# dac.net
KiCad netlist of a schematic drawn in EAGLE
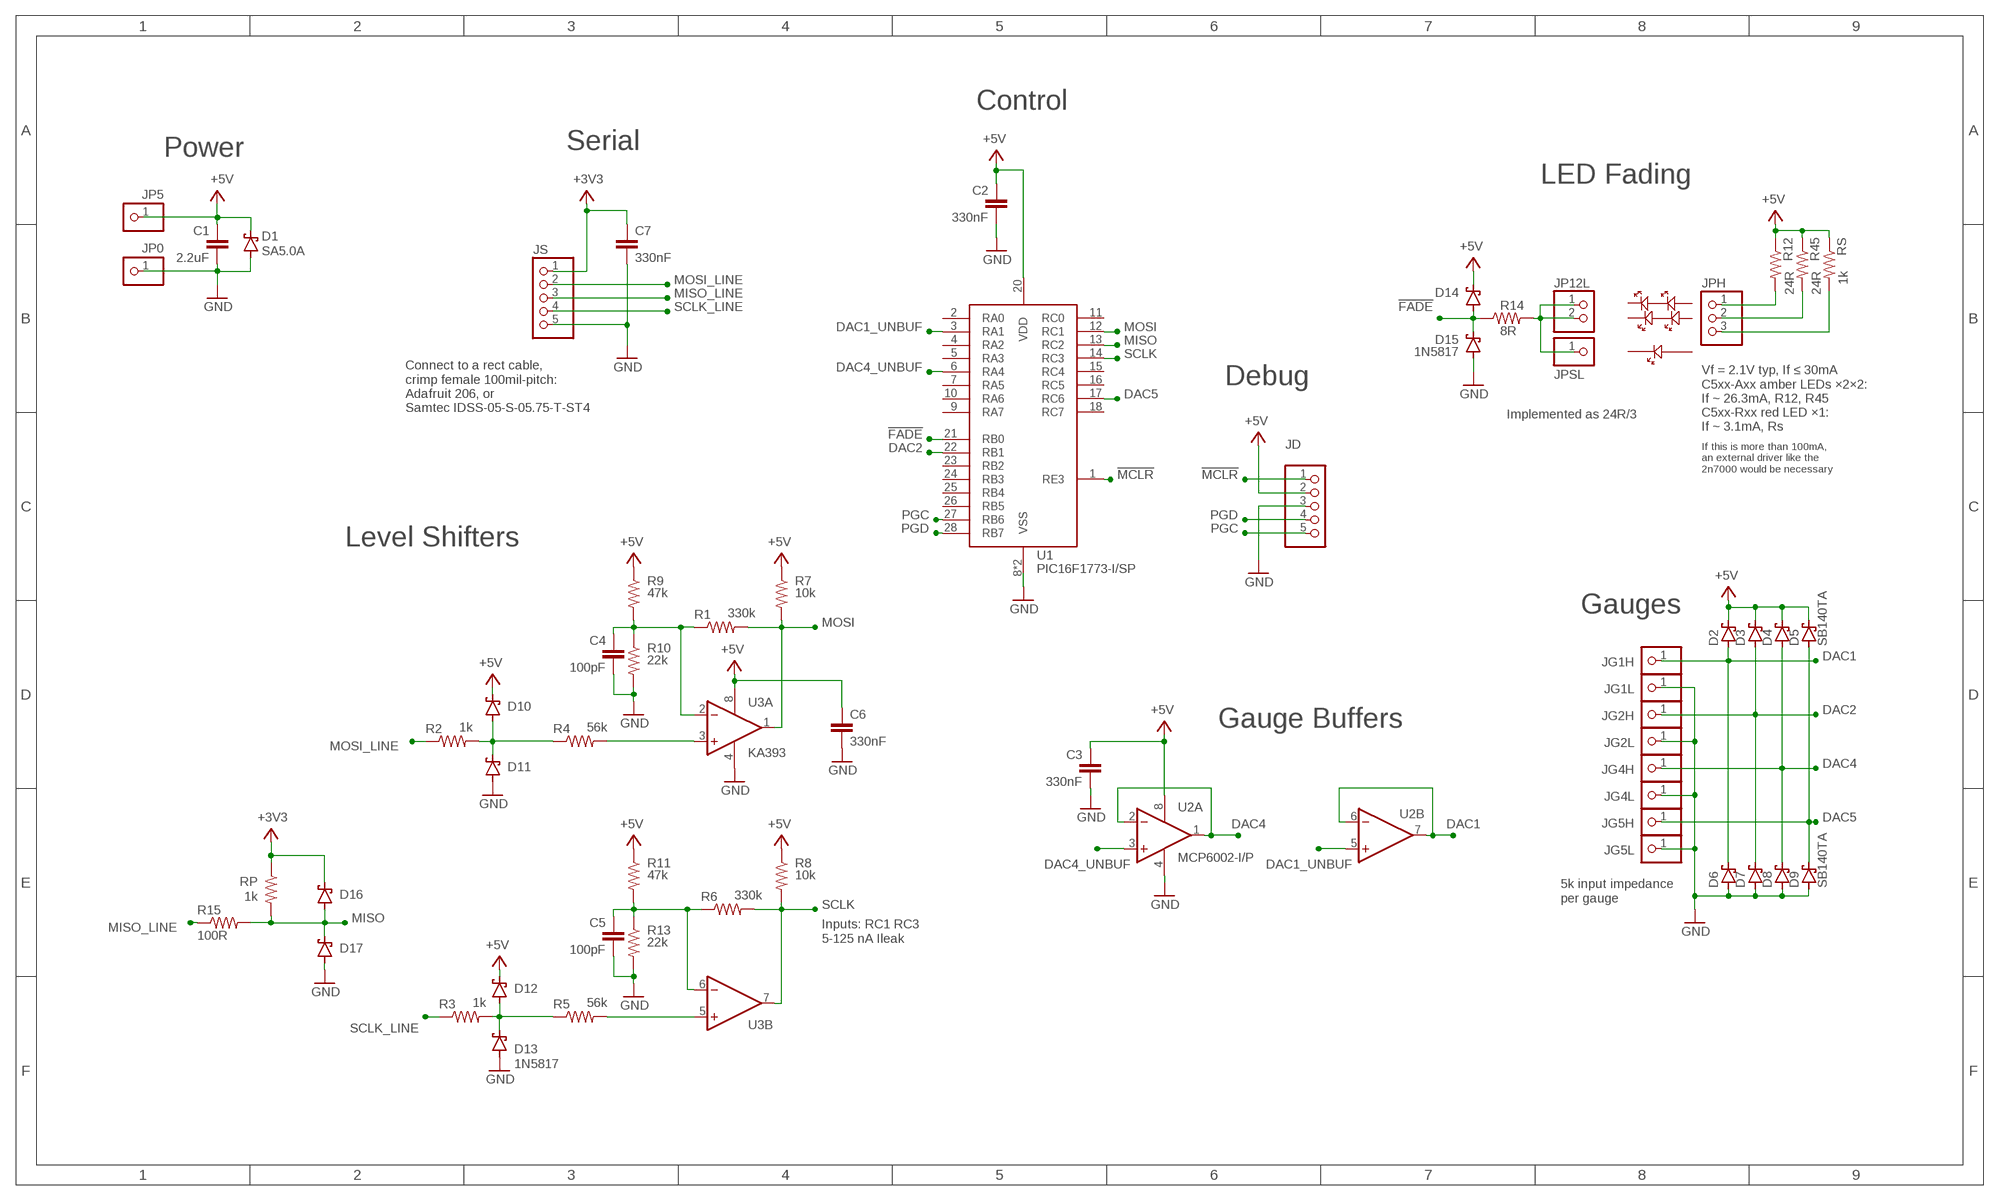
[diagram p0: schematic, sheet 1]

(export (version "E")
  (design (tool "Eeschema 10.0.6"))
  (components
    (comp (ref "C1")
      (value "2.2uF")
      (footprint "eagle-import:C050-024X044")
      (libsource (lib "eagle-import") (part "C-EU050-024X044"))
    )
    (comp (ref "C2")
      (value "330nF")
      (footprint "eagle-import:C050-024X044")
      (libsource (lib "eagle-import") (part "C-EU050-024X044"))
    )
    (comp (ref "C3")
      (value "330nF")
      (footprint "eagle-import:C050-024X044")
      (libsource (lib "eagle-import") (part "C-EU050-024X044"))
    )
    (comp (ref "C4")
      (value "100pF")
      (footprint "eagle-import:C050-024X044")
      (libsource (lib "eagle-import") (part "C-EU050-024X044"))
    )
    (comp (ref "C5")
      (value "100pF")
      (footprint "eagle-import:C050-024X044")
      (libsource (lib "eagle-import") (part "C-EU050-024X044"))
    )
    (comp (ref "C6")
      (value "330nF")
      (footprint "eagle-import:C050-024X044")
      (libsource (lib "eagle-import") (part "C-EU050-024X044"))
    )
    (comp (ref "C7")
      (value "330nF")
      (footprint "eagle-import:C050-024X044")
      (libsource (lib "eagle-import") (part "C-EU050-024X044"))
    )
    (comp (ref "D1")
      (value "SA5.0A")
      (footprint "eagle-import:ZDIO-2.5")
      (libsource (lib "eagle-import") (part "SB-V120"))
    )
    (comp (ref "D2")
      (value "SB140TA")
      (footprint "eagle-import:DO41-7.6")
      (libsource (lib "eagle-import") (part "SB140"))
    )
    (comp (ref "D3")
      (value "SB140TA")
      (footprint "eagle-import:DO41-7.6")
      (libsource (lib "eagle-import") (part "SB140"))
    )
    (comp (ref "D4")
      (value "SB140TA")
      (footprint "eagle-import:DO41-7.6")
      (libsource (lib "eagle-import") (part "SB140"))
    )
    (comp (ref "D5")
      (value "SB140TA")
      (footprint "eagle-import:DO41-7.6")
      (libsource (lib "eagle-import") (part "SB140"))
    )
    (comp (ref "D6")
      (value "SB140TA")
      (footprint "eagle-import:DO41-7.6")
      (libsource (lib "eagle-import") (part "SB140"))
    )
    (comp (ref "D7")
      (value "SB140TA")
      (footprint "eagle-import:DO41-7.6")
      (libsource (lib "eagle-import") (part "1N5817-B"))
    )
    (comp (ref "D8")
      (value "SB140TA")
      (footprint "eagle-import:DO41-7.6")
      (libsource (lib "eagle-import") (part "1N5817-B"))
    )
    (comp (ref "D9")
      (value "SB140TA")
      (footprint "eagle-import:DO41-7.6")
      (libsource (lib "eagle-import") (part "1N5817-B"))
    )
    (comp (ref "D10")
      (value "1N5817-H76")
      (footprint "eagle-import:DO41-7.6")
      (libsource (lib "eagle-import") (part "1N581-H767"))
    )
    (comp (ref "D11")
      (value "1N5817-V")
      (footprint "eagle-import:ZDIO-2.5")
      (libsource (lib "eagle-import") (part "1N581-V7"))
    )
    (comp (ref "D12")
      (value "1N5817-T")
      (footprint "eagle-import:DO41-7.6")
      (libsource (lib "eagle-import") (part "1N5817-T"))
    )
    (comp (ref "D13")
      (value "1N5817")
      (footprint "eagle-import:DO41-10")
      (libsource (lib "eagle-import") (part "1N581-H107"))
    )
    (comp (ref "D14")
      (value "1N5817")
      (footprint "eagle-import:ZDIO-2.5")
      (libsource (lib "eagle-import") (part "SB-V140"))
    )
    (comp (ref "D15")
      (value "1N5817")
      (footprint "eagle-import:ZDIO-2.5")
      (libsource (lib "eagle-import") (part "SB-V140"))
    )
    (comp (ref "D16")
      (value "1N5817-T")
      (footprint "eagle-import:DO41-7.6")
      (libsource (lib "eagle-import") (part "1N5817-T"))
    )
    (comp (ref "D17")
      (value "1N5817-T")
      (footprint "eagle-import:DO41-7.6")
      (libsource (lib "eagle-import") (part "1N5817-T"))
    )
    (comp (ref "JD")
      (value "PINHD-1X5")
      (footprint "eagle-import:1X05")
      (libsource (lib "eagle-import") (part "PINHD-1X5"))
    )
    (comp (ref "JG1H")
      (value "PINHD-1X1")
      (footprint "eagle-import:1X01")
      (libsource (lib "eagle-import") (part "PINHD-1X1"))
    )
    (comp (ref "JG1L")
      (value "PINHD-1X1")
      (footprint "eagle-import:1X01")
      (libsource (lib "eagle-import") (part "PINHD-1X1"))
    )
    (comp (ref "JG2H")
      (value "PINHD-1X1")
      (footprint "eagle-import:1X01")
      (libsource (lib "eagle-import") (part "PINHD-1X1"))
    )
    (comp (ref "JG2L")
      (value "PINHD-1X1")
      (footprint "eagle-import:1X01")
      (libsource (lib "eagle-import") (part "PINHD-1X1"))
    )
    (comp (ref "JG4H")
      (value "PINHD-1X1")
      (footprint "eagle-import:1X01")
      (libsource (lib "eagle-import") (part "PINHD-1X1"))
    )
    (comp (ref "JG4L")
      (value "PINHD-1X1")
      (footprint "eagle-import:1X01")
      (libsource (lib "eagle-import") (part "PINHD-1X1"))
    )
    (comp (ref "JG5H")
      (value "PINHD-1X1")
      (footprint "eagle-import:1X01")
      (libsource (lib "eagle-import") (part "PINHD-1X1"))
    )
    (comp (ref "JG5L")
      (value "PINHD-1X1")
      (footprint "eagle-import:1X01")
      (libsource (lib "eagle-import") (part "PINHD-1X1"))
    )
    (comp (ref "JP0")
      (value "PINHD-1X1")
      (footprint "eagle-import:1X01")
      (libsource (lib "eagle-import") (part "PINHD-1X1"))
    )
    (comp (ref "JP5")
      (value "PINHD-1X1")
      (footprint "eagle-import:1X01")
      (libsource (lib "eagle-import") (part "PINHD-1X1"))
    )
    (comp (ref "JP12L")
      (value "PINHD-1X2")
      (footprint "eagle-import:1X02")
      (libsource (lib "eagle-import") (part "PINHD-1X2"))
    )
    (comp (ref "JPH")
      (value "PINHD-1X3")
      (footprint "eagle-import:1X03")
      (libsource (lib "eagle-import") (part "PINHD-1X3"))
    )
    (comp (ref "JPSL")
      (value "PINHD-1X1")
      (footprint "eagle-import:1X01")
      (libsource (lib "eagle-import") (part "PINHD-1X1"))
    )
    (comp (ref "JS")
      (value "PINHD-1X5")
      (footprint "eagle-import:1X05")
      (libsource (lib "eagle-import") (part "PINHD-1X5"))
    )
    (comp (ref "R1")
      (value "330k")
      (footprint "eagle-import:0207_2V")
      (libsource (lib "eagle-import") (part "R-US_0207/2V"))
    )
    (comp (ref "R2")
      (value "1k")
      (footprint "eagle-import:0204_7")
      (libsource (lib "eagle-import") (part "R-US_0204/7"))
    )
    (comp (ref "R3")
      (value "1k")
      (footprint "eagle-import:0207_10")
      (libsource (lib "eagle-import") (part "R-US_0207/10"))
    )
    (comp (ref "R4")
      (value "56k")
      (footprint "eagle-import:0207_10")
      (libsource (lib "eagle-import") (part "R-US_0207/10"))
    )
    (comp (ref "R5")
      (value "56k")
      (footprint "eagle-import:0207_12")
      (libsource (lib "eagle-import") (part "R-US_0207/12"))
    )
    (comp (ref "R6")
      (value "330k")
      (footprint "eagle-import:0207_2V")
      (libsource (lib "eagle-import") (part "R-US_0207/2V"))
    )
    (comp (ref "R7")
      (value "10k")
      (footprint "eagle-import:0207_2V")
      (libsource (lib "eagle-import") (part "R-US_0207/2V"))
    )
    (comp (ref "R8")
      (value "10k")
      (footprint "eagle-import:0207_2V")
      (libsource (lib "eagle-import") (part "R-US_0207/2V"))
    )
    (comp (ref "R9")
      (value "47k")
      (footprint "eagle-import:0207_7")
      (libsource (lib "eagle-import") (part "R-US_0207/7"))
    )
    (comp (ref "R10")
      (value "22k")
      (footprint "eagle-import:0207_5V")
      (libsource (lib "eagle-import") (part "R-US_0207/5V"))
    )
    (comp (ref "R11")
      (value "47k")
      (footprint "eagle-import:0207_5V")
      (libsource (lib "eagle-import") (part "R-US_0207/5V"))
    )
    (comp (ref "R12")
      (value "24R")
      (footprint "eagle-import:0207_2V")
      (libsource (lib "eagle-import") (part "R-US_0207/2V"))
    )
    (comp (ref "R13")
      (value "22k")
      (footprint "eagle-import:0207_5V")
      (libsource (lib "eagle-import") (part "R-US_0207/5V"))
    )
    (comp (ref "R14")
      (value "8R")
      (footprint "eagle-import:0207_15")
      (libsource (lib "eagle-import") (part "R-US_0207/15"))
    )
    (comp (ref "R15")
      (value "100R")
      (footprint "eagle-import:0207_10")
      (libsource (lib "eagle-import") (part "R-US_0207/10"))
    )
    (comp (ref "R45")
      (value "24R")
      (footprint "eagle-import:0207_2V")
      (libsource (lib "eagle-import") (part "R-US_0207/2V"))
    )
    (comp (ref "RP")
      (value "1k")
      (footprint "eagle-import:0207_5V")
      (libsource (lib "eagle-import") (part "R-US_0207/5V"))
    )
    (comp (ref "RS")
      (value "1k")
      (footprint "eagle-import:0207_2V")
      (libsource (lib "eagle-import") (part "R-US_0207/2V"))
    )
    (comp (ref "U1")
      (value "PIC16F1773-I/SP")
      (footprint "eagle-import:DIL28-3")
      (libsource (lib "eagle-import") (part "PIC16F177/SP3-I"))
    )
    (comp (ref "U2")
      (value "MCP6002-I/P")
      (footprint "eagle-import:DIL08")
      (libsource (lib "eagle-import") (part "MCP602P"))
    )
    (comp (ref "U3")
      (value "KA393")
      (footprint "eagle-import:DIL08")
      (libsource (lib "eagle-import") (part "LM393N"))
    )
  )
  (nets
    (net (code "1") (name "+3V3") (class "Default")
      (node (ref "C7") (pin "1") (pinfunction "1_1") (pintype "passive"))
      (node (ref "D16") (pin "C") (pinfunction "C_C") (pintype "passive"))
      (node (ref "JS") (pin "1") (pinfunction "1_1") (pintype "passive"))
      (node (ref "RP") (pin "1") (pinfunction "1_1") (pintype "passive"))
    )
    (net (code "2") (name "+5V") (class "Default")
      (node (ref "C1") (pin "1") (pinfunction "1_1") (pintype "passive"))
      (node (ref "C2") (pin "1") (pinfunction "1_1") (pintype "passive"))
      (node (ref "C3") (pin "1") (pinfunction "1_1") (pintype "passive"))
      (node (ref "C6") (pin "1") (pinfunction "1_1") (pintype "passive"))
      (node (ref "D1") (pin "C") (pinfunction "C_C") (pintype "passive"))
      (node (ref "D10") (pin "C") (pinfunction "C_C") (pintype "passive"))
      (node (ref "D12") (pin "C") (pinfunction "C_C") (pintype "passive"))
      (node (ref "D14") (pin "C") (pinfunction "C_C") (pintype "passive"))
      (node (ref "D2") (pin "C") (pinfunction "C_C") (pintype "passive"))
      (node (ref "D3") (pin "C") (pinfunction "C_C") (pintype "passive"))
      (node (ref "D4") (pin "C") (pinfunction "C_C") (pintype "passive"))
      (node (ref "D5") (pin "C") (pinfunction "C_C") (pintype "passive"))
      (node (ref "JD") (pin "2") (pinfunction "2_2") (pintype "passive"))
      (node (ref "JP5") (pin "1") (pinfunction "1_1") (pintype "passive"))
      (node (ref "R11") (pin "1") (pinfunction "1_1") (pintype "passive"))
      (node (ref "R12") (pin "1") (pinfunction "1_1") (pintype "passive"))
      (node (ref "R45") (pin "1") (pinfunction "1_1") (pintype "passive"))
      (node (ref "R7") (pin "1") (pinfunction "1_1") (pintype "passive"))
      (node (ref "R8") (pin "1") (pinfunction "1_1") (pintype "passive"))
      (node (ref "R9") (pin "1") (pinfunction "1_1") (pintype "passive"))
      (node (ref "RS") (pin "1") (pinfunction "1_1") (pintype "passive"))
      (node (ref "U1") (pin "20") (pinfunction "VDD_20") (pintype "power_in"))
      (node (ref "U2") (pin "8") (pinfunction "V+_8") (pintype "power_in"))
      (node (ref "U3") (pin "8") (pinfunction "V+_8") (pintype "power_in"))
    )
    (net (code "3") (name "/DAC1") (class "Default")
      (node (ref "D2") (pin "A") (pinfunction "A_A") (pintype "passive"))
      (node (ref "D6") (pin "C") (pinfunction "C_C") (pintype "passive"))
      (node (ref "JG1H") (pin "1") (pinfunction "1_1") (pintype "passive"))
      (node (ref "U2") (pin "6") (pinfunction "-IN_6") (pintype "input"))
      (node (ref "U2") (pin "7") (pinfunction "OUT_7") (pintype "output"))
    )
    (net (code "4") (name "/DAC1_UNBUF") (class "Default")
      (node (ref "U1") (pin "3") (pinfunction "RA1_3") (pintype "bidirectional"))
      (node (ref "U2") (pin "5") (pinfunction "+IN_5") (pintype "input"))
    )
    (net (code "5") (name "/DAC2") (class "Default")
      (node (ref "D3") (pin "A") (pinfunction "A_A") (pintype "passive"))
      (node (ref "D7") (pin "C") (pinfunction "C_C") (pintype "passive"))
      (node (ref "JG2H") (pin "1") (pinfunction "1_1") (pintype "passive"))
      (node (ref "U1") (pin "22") (pinfunction "RB1_22") (pintype "bidirectional"))
    )
    (net (code "6") (name "/DAC4") (class "Default")
      (node (ref "D4") (pin "A") (pinfunction "A_A") (pintype "passive"))
      (node (ref "D8") (pin "C") (pinfunction "C_C") (pintype "passive"))
      (node (ref "JG4H") (pin "1") (pinfunction "1_1") (pintype "passive"))
      (node (ref "U2") (pin "1") (pinfunction "OUT_1") (pintype "output"))
      (node (ref "U2") (pin "2") (pinfunction "-IN_2") (pintype "input"))
    )
    (net (code "7") (name "/DAC4_UNBUF") (class "Default")
      (node (ref "U1") (pin "6") (pinfunction "RA4_6") (pintype "bidirectional"))
      (node (ref "U2") (pin "3") (pinfunction "+IN_3") (pintype "input"))
    )
    (net (code "8") (name "/DAC5") (class "Default")
      (node (ref "D5") (pin "A") (pinfunction "A_A") (pintype "passive"))
      (node (ref "D9") (pin "C") (pinfunction "C_C") (pintype "passive"))
      (node (ref "JG5H") (pin "1") (pinfunction "1_1") (pintype "passive"))
      (node (ref "U1") (pin "17") (pinfunction "RC6_17") (pintype "bidirectional"))
    )
    (net (code "9") (name "/MISO") (class "Default")
      (node (ref "D16") (pin "A") (pinfunction "A_A") (pintype "passive"))
      (node (ref "D17") (pin "C") (pinfunction "C_C") (pintype "passive"))
      (node (ref "R15") (pin "2") (pinfunction "2_2") (pintype "passive"))
      (node (ref "RP") (pin "2") (pinfunction "2_2") (pintype "passive"))
      (node (ref "U1") (pin "13") (pinfunction "RC2_13") (pintype "bidirectional"))
    )
    (net (code "10") (name "/MISO_LINE") (class "Default")
      (node (ref "JS") (pin "3") (pinfunction "3_3") (pintype "passive"))
      (node (ref "R15") (pin "1") (pinfunction "1_1") (pintype "passive"))
    )
    (net (code "11") (name "/MOSI") (class "Default")
      (node (ref "R1") (pin "2") (pinfunction "2_2") (pintype "passive"))
      (node (ref "R7") (pin "2") (pinfunction "2_2") (pintype "passive"))
      (node (ref "U1") (pin "12") (pinfunction "RC1_12") (pintype "bidirectional"))
      (node (ref "U3") (pin "1") (pinfunction "OUT_1") (pintype "output"))
    )
    (net (code "12") (name "/MOSI_LINE") (class "Default")
      (node (ref "JS") (pin "2") (pinfunction "2_2") (pintype "passive"))
      (node (ref "R2") (pin "1") (pinfunction "1_1") (pintype "passive"))
    )
    (net (code "13") (name "/PGC") (class "Default")
      (node (ref "JD") (pin "5") (pinfunction "5_5") (pintype "passive"))
      (node (ref "U1") (pin "27") (pinfunction "RB6_27") (pintype "bidirectional"))
    )
    (net (code "14") (name "/PGD") (class "Default")
      (node (ref "JD") (pin "4") (pinfunction "4_4") (pintype "passive"))
      (node (ref "U1") (pin "28") (pinfunction "RB7_28") (pintype "bidirectional"))
    )
    (net (code "15") (name "/SCLK") (class "Default")
      (node (ref "R6") (pin "2") (pinfunction "2_2") (pintype "passive"))
      (node (ref "R8") (pin "2") (pinfunction "2_2") (pintype "passive"))
      (node (ref "U1") (pin "14") (pinfunction "RC3_14") (pintype "bidirectional"))
      (node (ref "U3") (pin "7") (pinfunction "OUT_7") (pintype "output"))
    )
    (net (code "16") (name "/SCLK_LINE") (class "Default")
      (node (ref "JS") (pin "4") (pinfunction "4_4") (pintype "passive"))
      (node (ref "R3") (pin "1") (pinfunction "1_1") (pintype "passive"))
    )
    (net (code "17") (name "/~{FADE}") (class "Default")
      (node (ref "D14") (pin "A") (pinfunction "A_A") (pintype "passive"))
      (node (ref "D15") (pin "C") (pinfunction "C_C") (pintype "passive"))
      (node (ref "R14") (pin "1") (pinfunction "1_1") (pintype "passive"))
      (node (ref "U1") (pin "21") (pinfunction "RB0_21") (pintype "bidirectional"))
    )
    (net (code "18") (name "/~{MCLR}") (class "Default")
      (node (ref "JD") (pin "1") (pinfunction "1_1") (pintype "passive"))
      (node (ref "U1") (pin "1") (pinfunction "RE3_1") (pintype "bidirectional"))
    )
    (net (code "19") (name "GND") (class "Default")
      (node (ref "C1") (pin "2") (pinfunction "2_2") (pintype "passive"))
      (node (ref "C2") (pin "2") (pinfunction "2_2") (pintype "passive"))
      (node (ref "C3") (pin "2") (pinfunction "2_2") (pintype "passive"))
      (node (ref "C4") (pin "2") (pinfunction "2_2") (pintype "passive"))
      (node (ref "C5") (pin "2") (pinfunction "2_2") (pintype "passive"))
      (node (ref "C6") (pin "2") (pinfunction "2_2") (pintype "passive"))
      (node (ref "C7") (pin "2") (pinfunction "2_2") (pintype "passive"))
      (node (ref "D1") (pin "A") (pinfunction "A_A") (pintype "passive"))
      (node (ref "D11") (pin "A") (pinfunction "A_A") (pintype "passive"))
      (node (ref "D13") (pin "A") (pinfunction "A_A") (pintype "passive"))
      (node (ref "D15") (pin "A") (pinfunction "A_A") (pintype "passive"))
      (node (ref "D17") (pin "A") (pinfunction "A_A") (pintype "passive"))
      (node (ref "D6") (pin "A") (pinfunction "A_A") (pintype "passive"))
      (node (ref "D7") (pin "A") (pinfunction "A_A") (pintype "passive"))
      (node (ref "D8") (pin "A") (pinfunction "A_A") (pintype "passive"))
      (node (ref "D9") (pin "A") (pinfunction "A_A") (pintype "passive"))
      (node (ref "JD") (pin "3") (pinfunction "3_3") (pintype "passive"))
      (node (ref "JG1L") (pin "1") (pinfunction "1_1") (pintype "passive"))
      (node (ref "JG2L") (pin "1") (pinfunction "1_1") (pintype "passive"))
      (node (ref "JG4L") (pin "1") (pinfunction "1_1") (pintype "passive"))
      (node (ref "JG5L") (pin "1") (pinfunction "1_1") (pintype "passive"))
      (node (ref "JP0") (pin "1") (pinfunction "1_1") (pintype "passive"))
      (node (ref "JS") (pin "5") (pinfunction "5_5") (pintype "passive"))
      (node (ref "R10") (pin "2") (pinfunction "2_2") (pintype "passive"))
      (node (ref "R13") (pin "2") (pinfunction "2_2") (pintype "passive"))
      (node (ref "U1") (pin "19") (pinfunction "VSS_19") (pintype "power_in"))
      (node (ref "U1") (pin "8") (pinfunction "VSS_8") (pintype "power_in"))
      (node (ref "U2") (pin "4") (pinfunction "V-_4") (pintype "power_in"))
      (node (ref "U3") (pin "4") (pinfunction "V-_4") (pintype "power_in"))
    )
    (net (code "20") (name "Net-(D10-PadA)") (class "Default")
      (node (ref "D10") (pin "A") (pinfunction "A_A") (pintype "passive"))
      (node (ref "D11") (pin "C") (pinfunction "C_C") (pintype "passive"))
      (node (ref "R2") (pin "2") (pinfunction "2_2") (pintype "passive"))
      (node (ref "R4") (pin "1") (pinfunction "1_1") (pintype "passive"))
    )
    (net (code "21") (name "Net-(D12-PadA)") (class "Default")
      (node (ref "D12") (pin "A") (pinfunction "A_A") (pintype "passive"))
      (node (ref "D13") (pin "C") (pinfunction "C_C") (pintype "passive"))
      (node (ref "R3") (pin "2") (pinfunction "2_2") (pintype "passive"))
      (node (ref "R5") (pin "1") (pinfunction "1_1") (pintype "passive"))
    )
    (net (code "22") (name "Net-(JP12L-Pad1)") (class "Default")
      (node (ref "JP12L") (pin "1") (pinfunction "1_1") (pintype "passive"))
      (node (ref "JP12L") (pin "2") (pinfunction "2_2") (pintype "passive"))
      (node (ref "JPSL") (pin "1") (pinfunction "1_1") (pintype "passive"))
      (node (ref "R14") (pin "2") (pinfunction "2_2") (pintype "passive"))
    )
    (net (code "23") (name "Net-(JPH-Pad1)") (class "Default")
      (node (ref "JPH") (pin "1") (pinfunction "1_1") (pintype "passive"))
      (node (ref "R12") (pin "2") (pinfunction "2_2") (pintype "passive"))
    )
    (net (code "24") (name "Net-(JPH-Pad2)") (class "Default")
      (node (ref "JPH") (pin "2") (pinfunction "2_2") (pintype "passive"))
      (node (ref "R45") (pin "2") (pinfunction "2_2") (pintype "passive"))
    )
    (net (code "25") (name "Net-(JPH-Pad3)") (class "Default")
      (node (ref "JPH") (pin "3") (pinfunction "3_3") (pintype "passive"))
      (node (ref "RS") (pin "2") (pinfunction "2_2") (pintype "passive"))
    )
    (net (code "26") (name "Net-(U3A-+IN)") (class "Default")
      (node (ref "R4") (pin "2") (pinfunction "2_2") (pintype "passive"))
      (node (ref "U3") (pin "3") (pinfunction "+IN_3") (pintype "input"))
    )
    (net (code "27") (name "Net-(U3A--IN)") (class "Default")
      (node (ref "C4") (pin "1") (pinfunction "1_1") (pintype "passive"))
      (node (ref "R1") (pin "1") (pinfunction "1_1") (pintype "passive"))
      (node (ref "R10") (pin "1") (pinfunction "1_1") (pintype "passive"))
      (node (ref "R9") (pin "2") (pinfunction "2_2") (pintype "passive"))
      (node (ref "U3") (pin "2") (pinfunction "-IN_2") (pintype "input"))
    )
    (net (code "28") (name "Net-(U3B-+IN)") (class "Default")
      (node (ref "R5") (pin "2") (pinfunction "2_2") (pintype "passive"))
      (node (ref "U3") (pin "5") (pinfunction "+IN_5") (pintype "input"))
    )
    (net (code "29") (name "Net-(U3B--IN)") (class "Default")
      (node (ref "C5") (pin "1") (pinfunction "1_1") (pintype "passive"))
      (node (ref "R11") (pin "2") (pinfunction "2_2") (pintype "passive"))
      (node (ref "R13") (pin "1") (pinfunction "1_1") (pintype "passive"))
      (node (ref "R6") (pin "1") (pinfunction "1_1") (pintype "passive"))
      (node (ref "U3") (pin "6") (pinfunction "-IN_6") (pintype "input"))
    )
    (net (code "30") (name "unconnected-(U1-RA0-Pad2)") (class "Default")
      (node (ref "U1") (pin "2") (pinfunction "RA0_2") (pintype "bidirectional"))
    )
    (net (code "31") (name "unconnected-(U1-RA2-Pad4)") (class "Default")
      (node (ref "U1") (pin "4") (pinfunction "RA2_4") (pintype "bidirectional"))
    )
    (net (code "32") (name "unconnected-(U1-RA3-Pad5)") (class "Default")
      (node (ref "U1") (pin "5") (pinfunction "RA3_5") (pintype "bidirectional"))
    )
    (net (code "33") (name "unconnected-(U1-RA5-Pad7)") (class "Default")
      (node (ref "U1") (pin "7") (pinfunction "RA5_7") (pintype "bidirectional"))
    )
    (net (code "34") (name "unconnected-(U1-RA6-Pad10)") (class "Default")
      (node (ref "U1") (pin "10") (pinfunction "RA6_10") (pintype "bidirectional"))
    )
    (net (code "35") (name "unconnected-(U1-RA7-Pad9)") (class "Default")
      (node (ref "U1") (pin "9") (pinfunction "RA7_9") (pintype "bidirectional"))
    )
    (net (code "36") (name "unconnected-(U1-RB2-Pad23)") (class "Default")
      (node (ref "U1") (pin "23") (pinfunction "RB2_23") (pintype "bidirectional"))
    )
    (net (code "37") (name "unconnected-(U1-RB3-Pad24)") (class "Default")
      (node (ref "U1") (pin "24") (pinfunction "RB3_24") (pintype "bidirectional"))
    )
    (net (code "38") (name "unconnected-(U1-RB4-Pad25)") (class "Default")
      (node (ref "U1") (pin "25") (pinfunction "RB4_25") (pintype "bidirectional"))
    )
    (net (code "39") (name "unconnected-(U1-RB5-Pad26)") (class "Default")
      (node (ref "U1") (pin "26") (pinfunction "RB5_26") (pintype "bidirectional"))
    )
    (net (code "40") (name "unconnected-(U1-RC0-Pad11)") (class "Default")
      (node (ref "U1") (pin "11") (pinfunction "RC0_11") (pintype "bidirectional"))
    )
    (net (code "41") (name "unconnected-(U1-RC4-Pad15)") (class "Default")
      (node (ref "U1") (pin "15") (pinfunction "RC4_15") (pintype "bidirectional"))
    )
    (net (code "42") (name "unconnected-(U1-RC5-Pad16)") (class "Default")
      (node (ref "U1") (pin "16") (pinfunction "RC5_16") (pintype "bidirectional"))
    )
    (net (code "43") (name "unconnected-(U1-RC7-Pad18)") (class "Default")
      (node (ref "U1") (pin "18") (pinfunction "RC7_18") (pintype "bidirectional"))
    )
  )
)
